# RPM_Inputs.net
KiCad netlist of a schematic drawn in Altium Designer
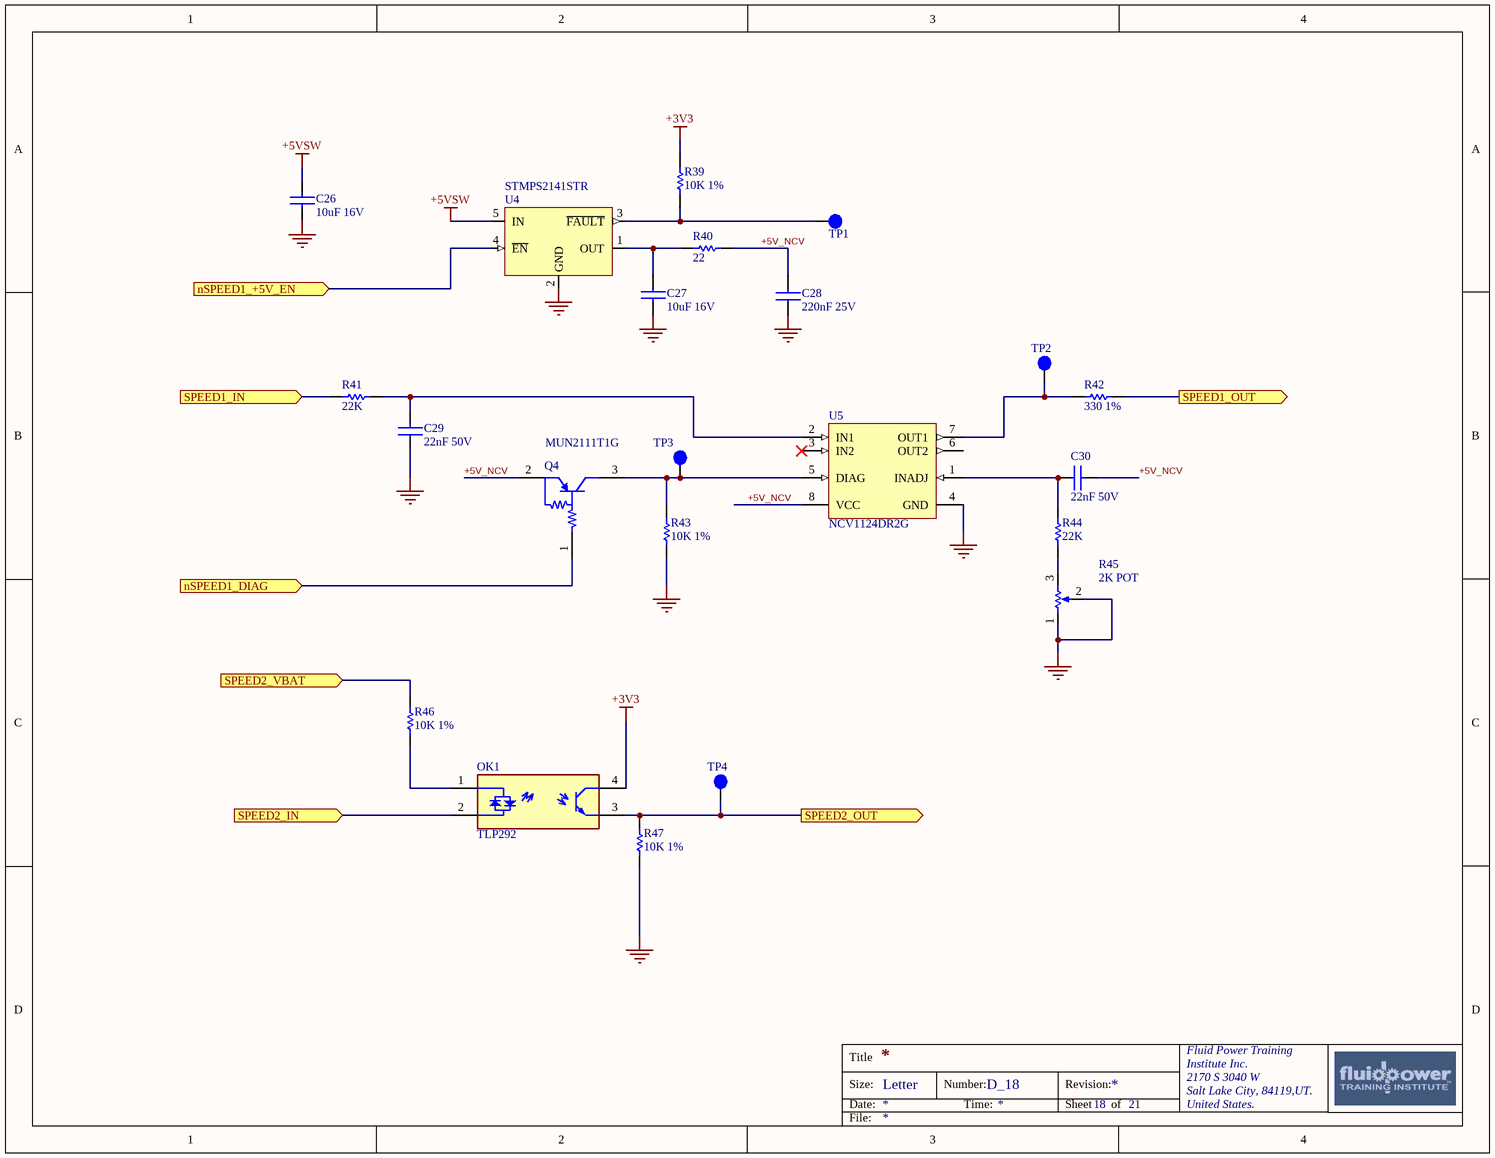
[diagram p0: RPM Inputs.SchDoc]

(export (version "E")
  (design (tool "Eeschema 10.0.6"))
  (components
    (comp (ref "C26")
      (value "10uF 16V")
      (footprint "C0805")
      (description "CAP CER 10UF 16V X5R 0805")
      (fields
        (field (name "MANUFACTURER") "Murata")
        (field (name "MANUFACTURER PART NUMBER") "GRM21BR61C106KE15L")
      )
      (libsource (lib "MCx") (part "GRM21BR61C106KE15L"))
    )
    (comp (ref "C27")
      (value "10uF 16V")
      (footprint "C0805")
      (description "CAP CER 10UF 16V X5R 0805")
      (fields
        (field (name "MANUFACTURER") "Murata")
        (field (name "MANUFACTURER PART NUMBER") "GRM21BR61C106KE15L")
      )
      (libsource (lib "MCx") (part "GRM21BR61C106KE15L"))
    )
    (comp (ref "C28")
      (value "220nF 25V")
      (footprint "C0805")
      (fields
        (field (name "MANUFACTURER") "Kyocera AVX")
        (field (name "MANUFACTURER PART NUMBER") "08053C224JAT2A")
        (field (name "TOLERANCE") "5%")
      )
      (libsource (lib "MCx") (part "08053C224JAT2A"))
    )
    (comp (ref "C29")
      (value "22nF 50V")
      (footprint "C0805")
      (description "KEMET 22nF Multilayer Ceramic Capacitor (MLCC) 50V dc 10% X7R dielectric max op. temp. 125C")
      (fields
        (field (name "MANUFACTURER") "KEMET")
        (field (name "MANUFACTURER PART NUMBER") "C0805C223K5RAC")
      )
      (libsource (lib "MCx") (part "C0805C223K5RAC"))
    )
    (comp (ref "C30")
      (value "22nF 50V")
      (footprint "C0805")
      (description "KEMET 22nF Multilayer Ceramic Capacitor (MLCC) 50V dc 10% X7R dielectric max op. temp. 125C")
      (fields
        (field (name "MANUFACTURER") "KEMET")
        (field (name "MANUFACTURER PART NUMBER") "C0805C223K5RAC")
      )
      (libsource (lib "MCx") (part "C0805C223K5RAC"))
    )
    (comp (ref "OK1")
      (value "TLP292")
      (footprint "SOIC127P700X220-4N")
      (description "OPTOISOLATOR 3.75KV TRANS 4-SO")
      (fields
        (field (name "MANUFACTURER") "Toshiba")
        (field (name "MANUFACTURER PART NUMBER") "TLP292(GB-TPL,E")
      )
      (libsource (lib "MCx") (part "TLP292(GB-TPL,E"))
    )
    (comp (ref "Q4")
      (value "MUN2111T1G")
      (footprint "ONSC-SC-59-3-318D-04_V")
      (description "TRANS PREBIAS PNP 230MW SC59")
      (fields (field (name "MANUFACTURER") "ON Semiconductor"))
      (libsource (lib "MCx") (part "MUN2111T1G"))
    )
    (comp (ref "R39")
      (value "10K 1%")
      (footprint "R0805")
      (fields
        (field (name "MANUFACTURER") "Vishay")
        (field (name "MANUFACTURER PART NUMBER") "CRCW080510K0FKEA")
        (field (name "TOLERANCE") "1%")
      )
      (libsource (lib "MCx") (part "CRCW080510K0FKEA"))
    )
    (comp (ref "R40")
      (value "22")
      (footprint "R0805")
      (description "Resistor;  Thick Film;  22 Ohms;  0.125 W;  5%;  SMT;  0805;  TCR 73 ppm/DegC;  Cut Tape")
      (fields
        (field (name "MANUFACTURER") "Vishay Dale")
        (field (name "MANUFACTURER PART NUMBER") "CRCW080522R0JNEA")
      )
      (libsource (lib "MCx") (part "CRCW080522R0JNEA"))
    )
    (comp (ref "R41")
      (value "22K")
      (footprint "R0805")
      (fields
        (field (name "MANUFACTURER") "Panasonic")
        (field (name "MANUFACTURER PART NUMBER") "ERJ6ENF2202V")
        (field (name "TOLERANCE") "1%")
      )
      (libsource (lib "MCx") (part "ERJ6ENF2202V"))
    )
    (comp (ref "R42")
      (value "330 1%")
      (footprint "R0805")
      (description "RES SMD 330 OHM 1% 1/8W 0805")
      (fields
        (field (name "MANUFACTURER") "Panasonic")
        (field (name "MANUFACTURER PART NUMBER") "ERJ-6ENF3300V")
      )
      (libsource (lib "MCx") (part "ERJ-6ENF3300V"))
    )
    (comp (ref "R43")
      (value "10K 1%")
      (footprint "R0805")
      (fields
        (field (name "MANUFACTURER") "Vishay")
        (field (name "MANUFACTURER PART NUMBER") "CRCW080510K0FKEA")
        (field (name "TOLERANCE") "1%")
      )
      (libsource (lib "MCx") (part "CRCW080510K0FKEA"))
    )
    (comp (ref "R44")
      (value "22K")
      (footprint "R0805")
      (fields
        (field (name "MANUFACTURER") "Panasonic")
        (field (name "MANUFACTURER PART NUMBER") "ERJ6ENF2202V")
        (field (name "TOLERANCE") "1%")
      )
      (libsource (lib "MCx") (part "ERJ6ENF2202V"))
    )
    (comp (ref "R45")
      (value "2K POT")
      (footprint "TC33X")
      (description "GLOVE, POLYAMIDE, L/FREE, PU, SIZE 6 - More Details")
      (fields (field (name "MANUFACTURER") "Bourns") (field (name "MANUFACTURER PART NUMBER") "TC33X-2-202E"))
      (libsource (lib "MCx") (part "TC33X-2-202E"))
    )
    (comp (ref "R46")
      (value "10K 1%")
      (footprint "R0805")
      (fields
        (field (name "MANUFACTURER") "Vishay")
        (field (name "MANUFACTURER PART NUMBER") "CRCW080510K0FKEA")
        (field (name "TOLERANCE") "1%")
      )
      (libsource (lib "MCx") (part "CRCW080510K0FKEA"))
    )
    (comp (ref "R47")
      (value "10K 1%")
      (footprint "R0805")
      (fields
        (field (name "MANUFACTURER") "Vishay")
        (field (name "MANUFACTURER PART NUMBER") "CRCW080510K0FKEA")
        (field (name "TOLERANCE") "1%")
      )
      (libsource (lib "MCx") (part "CRCW080510K0FKEA"))
    )
    (comp (ref "TP1")
      (value "T")
      (footprint "MC1:TESTPOINTSMD_1x1MM")
      (description "SMD Test Point")
      (libsource (lib "MC1") (part "TestPoint_SMD_1x1"))
    )
    (comp (ref "TP2")
      (value "T")
      (footprint "MC1:TESTPOINTSMD_1x1MM")
      (description "SMD Test Point")
      (libsource (lib "MC1") (part "TestPoint_SMD_1x1"))
    )
    (comp (ref "TP3")
      (value "T")
      (footprint "MC1:TESTPOINTSMD_1x1MM")
      (description "SMD Test Point")
      (libsource (lib "MC1") (part "TestPoint_SMD_1x1"))
    )
    (comp (ref "TP4")
      (value "T")
      (footprint "MC1:TESTPOINTSMD_1x1MM")
      (description "SMD Test Point")
      (libsource (lib "MC1") (part "TestPoint_SMD_1x1"))
    )
    (comp (ref "U4")
      (value "STMPS2141STR")
      (footprint "MC1:SOT95P280X145-5M")
      (description "IC PWR SWITCH 1CH 500MA SOT23-5")
      (fields (field (name "MANUFACTURER") "STMicroelectronics") (field (name "VOLTAGE") "5.5V"))
      (libsource (lib "MC1") (part "STMPS2141STR"))
    )
    (comp (ref "U5")
      (value "NCV1124DR2G")
      (footprint "ONSC-SOIC-8NB-8-751-07_V")
      (description "ON SEMICONDUCTOR - NCV1124DR2G - Variable Reluctance Sensor, 4.5 V-5.5 V supply, SOIC-8")
      (fields (field (name "MANUFACTURER") "ON Semiconductor"))
      (libsource (lib "MCx") (part "NCV1124DR2G"))
    )
  )
  (nets
    (net (code "1") (name "+3V3") (class "Default")
      (node (ref "OK1") (pin "4") (pinfunction "COLLECTOR_4") (pintype "passive"))
      (node (ref "R39") (pin "2") (pinfunction "2_2") (pintype "passive"))
    )
    (net (code "2") (name "+5VSW") (class "Default")
      (node (ref "C26") (pin "1") (pinfunction "1_1") (pintype "passive"))
      (node (ref "U4") (pin "5") (pinfunction "IN_5") (pintype "power_in"))
    )
    (net (code "3") (name "/+5V_NCV") (class "Default")
      (node (ref "C28") (pin "2") (pinfunction "2_2") (pintype "passive"))
      (node (ref "C30") (pin "2") (pinfunction "2_2") (pintype "passive"))
      (node (ref "Q4") (pin "2") (pinfunction "E_2") (pintype "passive"))
      (node (ref "R40") (pin "2") (pinfunction "2_2") (pintype "passive"))
      (node (ref "U5") (pin "8") (pinfunction "VCC_8") (pintype "power_in"))
    )
    (net (code "4") (name "/SPEED1_IN") (class "Default")
      (node (ref "R41") (pin "1") (pinfunction "1_1") (pintype "passive"))
    )
    (net (code "5") (name "/SPEED1_OUT") (class "Default")
      (node (ref "R42") (pin "2") (pinfunction "2_2") (pintype "passive"))
    )
    (net (code "6") (name "/SPEED2_IN") (class "Default")
      (node (ref "OK1") (pin "2") (pinfunction "A,C_2") (pintype "passive"))
    )
    (net (code "7") (name "/SPEED2_OUT") (class "Default")
      (node (ref "OK1") (pin "3") (pinfunction "EMITTER_3") (pintype "passive"))
      (node (ref "R47") (pin "2") (pinfunction "2_2") (pintype "passive"))
      (node (ref "TP4") (pin "1") (pinfunction "1_1") (pintype "passive"))
    )
    (net (code "8") (name "/SPEED2_VBAT") (class "Default")
      (node (ref "R46") (pin "2") (pinfunction "2_2") (pintype "passive"))
    )
    (net (code "9") (name "/nSPEED1_+5V_EN") (class "Default")
      (node (ref "U4") (pin "4") (pinfunction "~{EN}_4") (pintype "input"))
    )
    (net (code "10") (name "/nSPEED1_DIAG") (class "Default")
      (node (ref "Q4") (pin "1") (pinfunction "B_1") (pintype "passive"))
    )
    (net (code "11") (name "GND") (class "Default")
      (node (ref "C26") (pin "2") (pinfunction "2_2") (pintype "passive"))
      (node (ref "C27") (pin "2") (pinfunction "2_2") (pintype "passive"))
      (node (ref "C28") (pin "1") (pinfunction "1_1") (pintype "passive"))
      (node (ref "C29") (pin "1") (pinfunction "1_1") (pintype "passive"))
      (node (ref "R43") (pin "1") (pinfunction "1_1") (pintype "passive"))
      (node (ref "R45") (pin "1") (pinfunction "1_1") (pintype "passive"))
      (node (ref "R45") (pin "2") (pinfunction "2_2") (pintype "power_in"))
      (node (ref "R47") (pin "1") (pinfunction "1_1") (pintype "passive"))
      (node (ref "U4") (pin "2") (pinfunction "GND_2") (pintype "power_in"))
      (node (ref "U5") (pin "4") (pinfunction "GND_4") (pintype "power_in"))
    )
    (net (code "12") (name "Net-(OK1-C,A)") (class "Default")
      (node (ref "OK1") (pin "1") (pinfunction "C,A_1") (pintype "passive"))
      (node (ref "R46") (pin "1") (pinfunction "1_1") (pintype "passive"))
    )
    (net (code "13") (name "Net-(Q4-C)") (class "Default")
      (node (ref "Q4") (pin "3") (pinfunction "C_3") (pintype "passive"))
      (node (ref "R43") (pin "2") (pinfunction "2_2") (pintype "passive"))
      (node (ref "TP3") (pin "1") (pinfunction "1_1") (pintype "passive"))
      (node (ref "U5") (pin "5") (pinfunction "DIAG_5") (pintype "input"))
    )
    (net (code "14") (name "Net-(R44-Pad1)") (class "Default")
      (node (ref "R44") (pin "1") (pinfunction "1_1") (pintype "passive"))
      (node (ref "R45") (pin "3") (pinfunction "3_3") (pintype "power_in"))
    )
    (net (code "15") (name "Net-(U4-OUT)") (class "Default")
      (node (ref "C27") (pin "1") (pinfunction "1_1") (pintype "passive"))
      (node (ref "R40") (pin "1") (pinfunction "1_1") (pintype "passive"))
      (node (ref "U4") (pin "1") (pinfunction "OUT_1") (pintype "power_in"))
    )
    (net (code "16") (name "Net-(U4-~{FAULT})") (class "Default")
      (node (ref "R39") (pin "1") (pinfunction "1_1") (pintype "passive"))
      (node (ref "TP1") (pin "1") (pinfunction "1_1") (pintype "passive"))
      (node (ref "U4") (pin "3") (pinfunction "~{FAULT}_3") (pintype "output"))
    )
    (net (code "17") (name "Net-(U5-IN1)") (class "Default")
      (node (ref "C29") (pin "2") (pinfunction "2_2") (pintype "passive"))
      (node (ref "R41") (pin "2") (pinfunction "2_2") (pintype "passive"))
      (node (ref "U5") (pin "2") (pinfunction "IN1_2") (pintype "input"))
    )
    (net (code "18") (name "Net-(U5-INADJ)") (class "Default")
      (node (ref "C30") (pin "1") (pinfunction "1_1") (pintype "passive"))
      (node (ref "R44") (pin "2") (pinfunction "2_2") (pintype "passive"))
      (node (ref "U5") (pin "1") (pinfunction "INADJ_1") (pintype "input"))
    )
    (net (code "19") (name "Net-(U5-OUT1)") (class "Default")
      (node (ref "R42") (pin "1") (pinfunction "1_1") (pintype "passive"))
      (node (ref "TP2") (pin "1") (pinfunction "1_1") (pintype "passive"))
      (node (ref "U5") (pin "7") (pinfunction "OUT1_7") (pintype "output"))
    )
    (net (code "20") (name "unconnected-(U5-IN2-Pad3)") (class "Default")
      (node (ref "U5") (pin "3") (pinfunction "IN2_3") (pintype "input+no_connect"))
    )
    (net (code "21") (name "unconnected-(U5-OUT2-Pad6)") (class "Default")
      (node (ref "U5") (pin "6") (pinfunction "OUT2_6") (pintype "output"))
    )
  )
)
